# faster-charger-sync.net
KiCad netlist of a schematic drawn in EAGLE
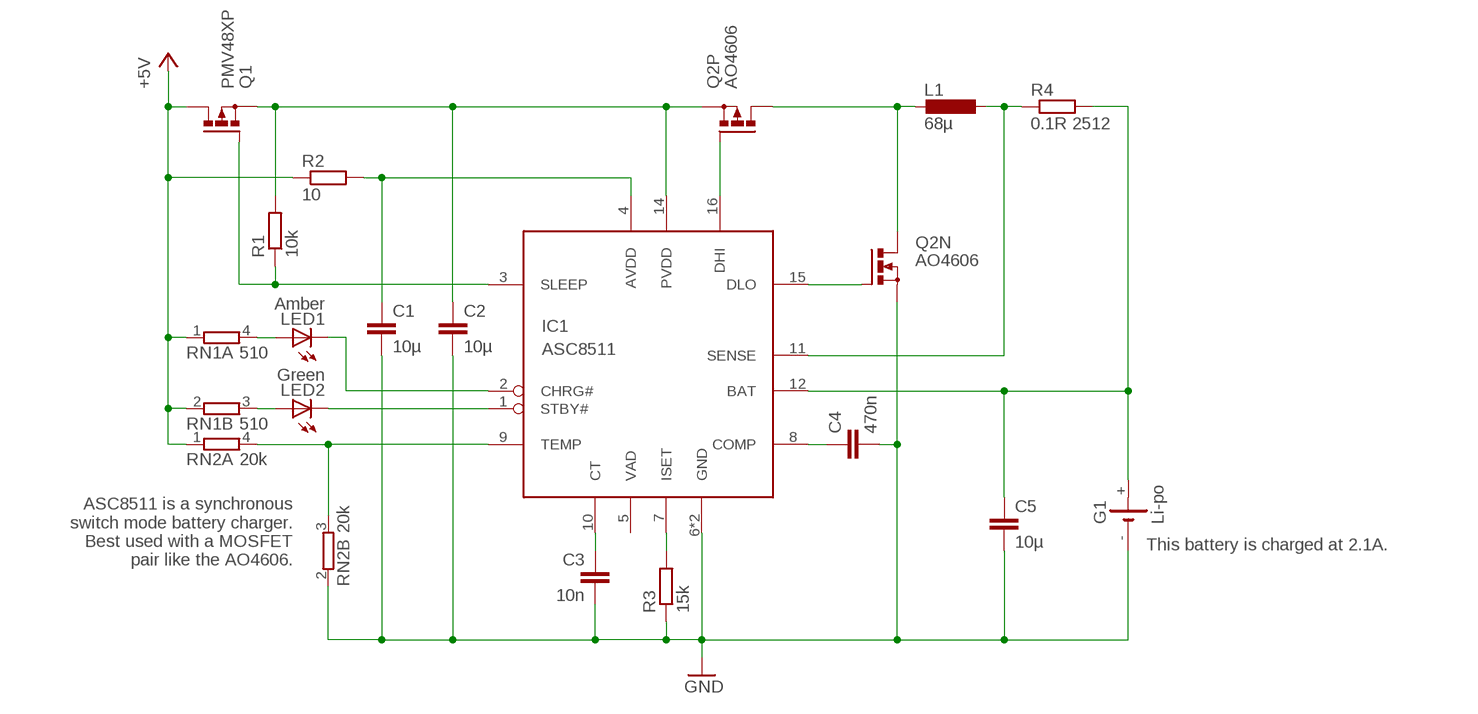
[diagram p0: schematic, sheet 1]

(export (version "E")
  (design (tool "Eeschema 10.0.6"))
  (components
    (comp (ref "C1")
      (value "10µ")
      (footprint "eagle-import:C0805")
      (libsource (lib "eagle-import") (part "C-EUC0805"))
    )
    (comp (ref "C2")
      (value "10µ")
      (footprint "eagle-import:C0805")
      (libsource (lib "eagle-import") (part "C-EUC0805"))
    )
    (comp (ref "C3")
      (value "10n")
      (footprint "eagle-import:C0603")
      (libsource (lib "eagle-import") (part "C-EUC0603"))
    )
    (comp (ref "C4")
      (value "470n")
      (footprint "eagle-import:C0603")
      (libsource (lib "eagle-import") (part "C-EUC0603"))
    )
    (comp (ref "C5")
      (value "10µ")
      (footprint "eagle-import:C0805")
      (libsource (lib "eagle-import") (part "C-EUC0805"))
    )
    (comp (ref "G1")
      (value "Li-po")
      (footprint "eagle-import:SL-150-1_2AA_PR")
      (libsource (lib "eagle-import") (part "SL-150-1/2AA/PR"))
    )
    (comp (ref "IC1")
      (value "ASC8511")
      (footprint "eagle-import:TSSOP16")
      (libsource (lib "eagle-import") (part "ASC8511"))
    )
    (comp (ref "L1")
      (value "68µ")
      (footprint "eagle-import:L2825P")
      (libsource (lib "eagle-import") (part "L-EUL2825P"))
    )
    (comp (ref "LED1")
      (value "Amber")
      (footprint "eagle-import:CHIP-LED0805")
      (libsource (lib "eagle-import") (part "LEDCHIP-LED0805"))
    )
    (comp (ref "LED2")
      (value "Green")
      (footprint "eagle-import:CHIP-LED0805")
      (libsource (lib "eagle-import") (part "LEDCHIP-LED0805"))
    )
    (comp (ref "Q1")
      (value "PMV48XP")
      (footprint "eagle-import:SOT23")
      (libsource (lib "eagle-import") (part "PMV48XP"))
    )
    (comp (ref "Q2")
      (value "AO4606")
      (footprint "eagle-import:SO-08M")
      (libsource (lib "eagle-import") (part "AO4606"))
    )
    (comp (ref "R1")
      (value "10k")
      (footprint "eagle-import:R0603")
      (libsource (lib "eagle-import") (part "R-EU_R0603"))
    )
    (comp (ref "R2")
      (value "10")
      (footprint "eagle-import:R0603")
      (libsource (lib "eagle-import") (part "R-EU_R0603"))
    )
    (comp (ref "R3")
      (value "15k")
      (footprint "eagle-import:R0603")
      (libsource (lib "eagle-import") (part "R-EU_R0603"))
    )
    (comp (ref "R4")
      (value "0.1R 2512")
      (footprint "eagle-import:R2512")
      (libsource (lib "eagle-import") (part "R-EU_R2512"))
    )
    (comp (ref "RN1")
      (value "510")
      (footprint "eagle-import:EXB34V")
      (libsource (lib "eagle-import") (part "2R-NEXB34V"))
    )
    (comp (ref "RN2")
      (value "20k")
      (footprint "eagle-import:EXB34V")
      (libsource (lib "eagle-import") (part "2R-NEXB34V"))
    )
  )
  (nets
    (net (code "1") (name "+5V") (class "Default")
      (node (ref "Q1") (pin "3") (pinfunction "D_3") (pintype "passive"))
      (node (ref "R2") (pin "1") (pinfunction "1_1") (pintype "passive"))
      (node (ref "RN1") (pin "1") (pinfunction "1_1") (pintype "passive"))
      (node (ref "RN1") (pin "2") (pinfunction "1_2") (pintype "passive"))
      (node (ref "RN2") (pin "1") (pinfunction "1_1") (pintype "passive"))
    )
    (net (code "2") (name "GND") (class "Default")
      (node (ref "C1") (pin "2") (pinfunction "2_2") (pintype "passive"))
      (node (ref "C2") (pin "2") (pinfunction "2_2") (pintype "passive"))
      (node (ref "C3") (pin "2") (pinfunction "2_2") (pintype "passive"))
      (node (ref "C4") (pin "2") (pinfunction "2_2") (pintype "passive"))
      (node (ref "C5") (pin "2") (pinfunction "2_2") (pintype "passive"))
      (node (ref "G1") (pin "-") (pinfunction "-_-") (pintype "passive"))
      (node (ref "IC1") (pin "13") (pinfunction "GND_13") (pintype "power_in"))
      (node (ref "IC1") (pin "6") (pinfunction "GND_6") (pintype "power_in"))
      (node (ref "Q2") (pin "1") (pinfunction "S_1") (pintype "passive"))
      (node (ref "R3") (pin "1") (pinfunction "1_1") (pintype "passive"))
      (node (ref "RN2") (pin "2") (pinfunction "1_2") (pintype "passive"))
    )
    (net (code "3") (name "Net-(IC1-AVDD)") (class "Default")
      (node (ref "C1") (pin "1") (pinfunction "1_1") (pintype "passive"))
      (node (ref "IC1") (pin "4") (pinfunction "AVDD_4") (pintype "power_in"))
      (node (ref "R2") (pin "2") (pinfunction "2_2") (pintype "passive"))
    )
    (net (code "4") (name "Net-(IC1-BAT)") (class "Default")
      (node (ref "C5") (pin "1") (pinfunction "1_1") (pintype "passive"))
      (node (ref "G1") (pin "+") (pinfunction "+_+") (pintype "passive"))
      (node (ref "IC1") (pin "12") (pinfunction "BAT_12") (pintype "input"))
      (node (ref "R4") (pin "2") (pinfunction "2_2") (pintype "passive"))
    )
    (net (code "5") (name "Net-(IC1-CHRG#)") (class "Default")
      (node (ref "IC1") (pin "2") (pinfunction "CHRG#_2") (pintype "output"))
      (node (ref "LED1") (pin "C") (pinfunction "C_C") (pintype "passive"))
    )
    (net (code "6") (name "Net-(IC1-COMP)") (class "Default")
      (node (ref "C4") (pin "1") (pinfunction "1_1") (pintype "passive"))
      (node (ref "IC1") (pin "8") (pinfunction "COMP_8") (pintype "bidirectional"))
    )
    (net (code "7") (name "Net-(IC1-CT)") (class "Default")
      (node (ref "C3") (pin "1") (pinfunction "1_1") (pintype "passive"))
      (node (ref "IC1") (pin "10") (pinfunction "CT_10") (pintype "bidirectional"))
    )
    (net (code "8") (name "Net-(IC1-DHI)") (class "Default")
      (node (ref "IC1") (pin "16") (pinfunction "DHI_16") (pintype "output"))
      (node (ref "Q2") (pin "5") (pinfunction "G_5") (pintype "passive"))
    )
    (net (code "9") (name "Net-(IC1-DLO)") (class "Default")
      (node (ref "IC1") (pin "15") (pinfunction "DLO_15") (pintype "output"))
      (node (ref "Q2") (pin "2") (pinfunction "G_2") (pintype "passive"))
    )
    (net (code "10") (name "Net-(IC1-ISET)") (class "Default")
      (node (ref "IC1") (pin "7") (pinfunction "ISET_7") (pintype "output"))
      (node (ref "R3") (pin "2") (pinfunction "2_2") (pintype "passive"))
    )
    (net (code "11") (name "Net-(IC1-PVDD)") (class "Default")
      (node (ref "C2") (pin "1") (pinfunction "1_1") (pintype "passive"))
      (node (ref "IC1") (pin "14") (pinfunction "PVDD_14") (pintype "power_in"))
      (node (ref "Q1") (pin "2") (pinfunction "S_2") (pintype "passive"))
      (node (ref "Q2") (pin "6") (pinfunction "S_6") (pintype "passive"))
      (node (ref "R1") (pin "2") (pinfunction "2_2") (pintype "passive"))
    )
    (net (code "12") (name "Net-(IC1-SENSE)") (class "Default")
      (node (ref "IC1") (pin "11") (pinfunction "SENSE_11") (pintype "input"))
      (node (ref "L1") (pin "1") (pinfunction "1_1") (pintype "passive"))
      (node (ref "R4") (pin "1") (pinfunction "1_1") (pintype "passive"))
    )
    (net (code "13") (name "Net-(IC1-SLEEP)") (class "Default")
      (node (ref "IC1") (pin "3") (pinfunction "SLEEP_3") (pintype "input"))
      (node (ref "Q1") (pin "1") (pinfunction "G_1") (pintype "passive"))
      (node (ref "R1") (pin "1") (pinfunction "1_1") (pintype "passive"))
    )
    (net (code "14") (name "Net-(IC1-STBY#)") (class "Default")
      (node (ref "IC1") (pin "1") (pinfunction "STBY#_1") (pintype "output"))
      (node (ref "LED2") (pin "C") (pinfunction "C_C") (pintype "passive"))
    )
    (net (code "15") (name "Net-(IC1-TEMP)") (class "Default")
      (node (ref "IC1") (pin "9") (pinfunction "TEMP_9") (pintype "input"))
      (node (ref "RN2") (pin "3") (pinfunction "2_3") (pintype "passive"))
      (node (ref "RN2") (pin "4") (pinfunction "2_4") (pintype "passive"))
    )
    (net (code "16") (name "Net-(L1-Pad2)") (class "Default")
      (node (ref "L1") (pin "2") (pinfunction "2_2") (pintype "passive"))
      (node (ref "Q2") (pin "3") (pinfunction "D_3") (pintype "passive"))
      (node (ref "Q2") (pin "4") (pinfunction "D_4") (pintype "passive"))
      (node (ref "Q2") (pin "7") (pinfunction "D_7") (pintype "passive"))
      (node (ref "Q2") (pin "8") (pinfunction "D_8") (pintype "passive"))
    )
    (net (code "17") (name "Net-(RN1A-2)") (class "Default")
      (node (ref "LED1") (pin "A") (pinfunction "A_A") (pintype "passive"))
      (node (ref "RN1") (pin "4") (pinfunction "2_4") (pintype "passive"))
    )
    (net (code "18") (name "Net-(RN1B-2)") (class "Default")
      (node (ref "LED2") (pin "A") (pinfunction "A_A") (pintype "passive"))
      (node (ref "RN1") (pin "3") (pinfunction "2_3") (pintype "passive"))
    )
    (net (code "19") (name "unconnected-(IC1-VAD-Pad5)") (class "Default")
      (node (ref "IC1") (pin "5") (pinfunction "VAD_5") (pintype "input"))
    )
  )
)
